# VerdiRT7_Sensor.net
KiCad netlist of a schematic drawn in EAGLE
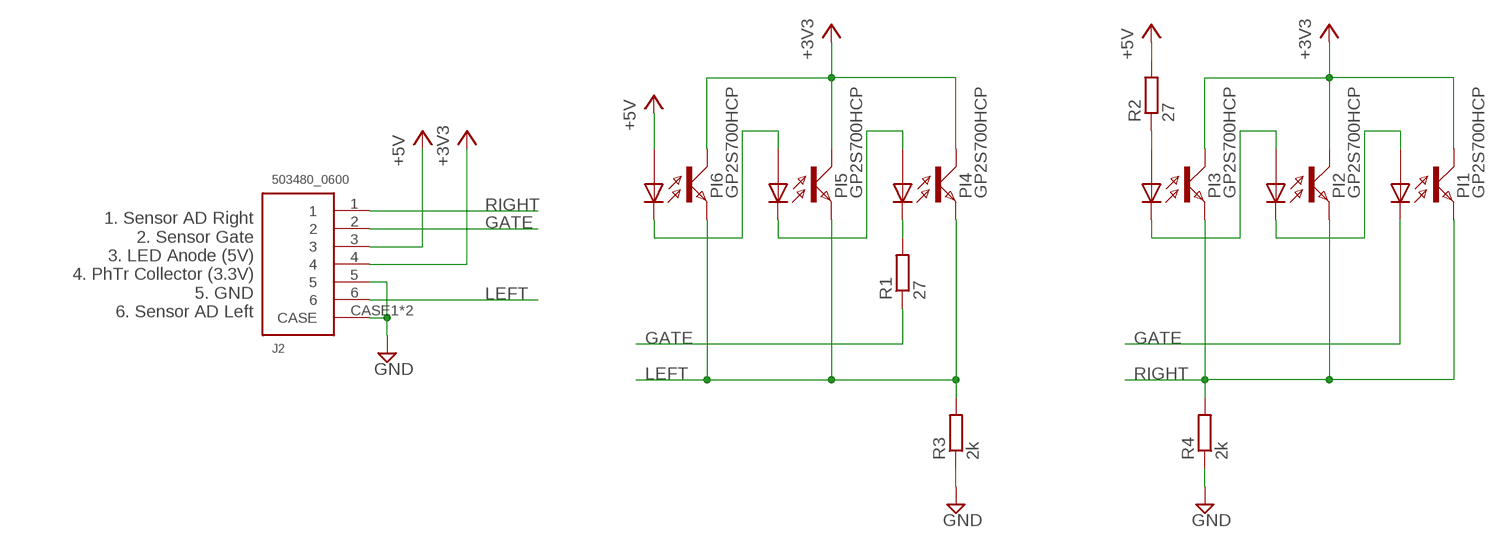
[diagram p0: schematic, sheet 1]

(export (version "E")
  (design (tool "Eeschema 10.0.6"))
  (components
    (comp (ref "J2")
      (value "503480_0600")
      (footprint "eagle-import:0600")
      (libsource (lib "eagle-import") (part "503480_0600"))
    )
    (comp (ref "PI1")
      (value "GP2S700HCP")
      (footprint "eagle-import:GP2S700")
      (libsource (lib "eagle-import") (part "GP2S700HCP"))
    )
    (comp (ref "PI2")
      (value "GP2S700HCP")
      (footprint "eagle-import:GP2S700")
      (libsource (lib "eagle-import") (part "GP2S700HCP"))
    )
    (comp (ref "PI3")
      (value "GP2S700HCP")
      (footprint "eagle-import:GP2S700")
      (libsource (lib "eagle-import") (part "GP2S700HCP"))
    )
    (comp (ref "PI4")
      (value "GP2S700HCP")
      (footprint "eagle-import:GP2S700")
      (libsource (lib "eagle-import") (part "GP2S700HCP"))
    )
    (comp (ref "PI5")
      (value "GP2S700HCP")
      (footprint "eagle-import:GP2S700")
      (libsource (lib "eagle-import") (part "GP2S700HCP"))
    )
    (comp (ref "PI6")
      (value "GP2S700HCP")
      (footprint "eagle-import:GP2S700")
      (libsource (lib "eagle-import") (part "GP2S700HCP"))
    )
    (comp (ref "R1")
      (value "27")
      (footprint "eagle-import:R0603")
      (libsource (lib "eagle-import") (part "R-EU_R0603"))
    )
    (comp (ref "R2")
      (value "27")
      (footprint "eagle-import:R0603")
      (libsource (lib "eagle-import") (part "R-EU_R0603"))
    )
    (comp (ref "R3")
      (value "2k")
      (footprint "eagle-import:R0603")
      (libsource (lib "eagle-import") (part "R-EU_R0603"))
    )
    (comp (ref "R4")
      (value "2k")
      (footprint "eagle-import:R0603")
      (libsource (lib "eagle-import") (part "R-EU_R0603"))
    )
  )
  (nets
    (net (code "1") (name "+3V3") (class "Default")
      (node (ref "J2") (pin "4") (pinfunction "4_4") (pintype "bidirectional"))
      (node (ref "PI1") (pin "COLLECTOR") (pinfunction "COLLECTOR_COLLECTOR") (pintype "passive"))
      (node (ref "PI2") (pin "COLLECTOR") (pinfunction "COLLECTOR_COLLECTOR") (pintype "passive"))
      (node (ref "PI3") (pin "COLLECTOR") (pinfunction "COLLECTOR_COLLECTOR") (pintype "passive"))
      (node (ref "PI4") (pin "COLLECTOR") (pinfunction "COLLECTOR_COLLECTOR") (pintype "passive"))
      (node (ref "PI5") (pin "COLLECTOR") (pinfunction "COLLECTOR_COLLECTOR") (pintype "passive"))
      (node (ref "PI6") (pin "COLLECTOR") (pinfunction "COLLECTOR_COLLECTOR") (pintype "passive"))
    )
    (net (code "2") (name "+5V") (class "Default")
      (node (ref "J2") (pin "3") (pinfunction "3_3") (pintype "bidirectional"))
      (node (ref "PI6") (pin "ANODE") (pinfunction "ANODE_ANODE") (pintype "passive"))
      (node (ref "R2") (pin "2") (pinfunction "2_2") (pintype "passive"))
    )
    (net (code "3") (name "/GATE") (class "Default")
      (node (ref "J2") (pin "2") (pinfunction "2_2") (pintype "bidirectional"))
      (node (ref "PI1") (pin "CATHODE") (pinfunction "CATHODE_CATHODE") (pintype "passive"))
      (node (ref "R1") (pin "1") (pinfunction "1_1") (pintype "passive"))
    )
    (net (code "4") (name "/LEFT") (class "Default")
      (node (ref "J2") (pin "6") (pinfunction "6_6") (pintype "bidirectional"))
      (node (ref "PI4") (pin "EMITTER") (pinfunction "EMITTER_EMITTER") (pintype "passive"))
      (node (ref "PI5") (pin "EMITTER") (pinfunction "EMITTER_EMITTER") (pintype "passive"))
      (node (ref "PI6") (pin "EMITTER") (pinfunction "EMITTER_EMITTER") (pintype "passive"))
      (node (ref "R3") (pin "2") (pinfunction "2_2") (pintype "passive"))
    )
    (net (code "5") (name "/RIGHT") (class "Default")
      (node (ref "J2") (pin "1") (pinfunction "1_1") (pintype "bidirectional"))
      (node (ref "PI1") (pin "EMITTER") (pinfunction "EMITTER_EMITTER") (pintype "passive"))
      (node (ref "PI2") (pin "EMITTER") (pinfunction "EMITTER_EMITTER") (pintype "passive"))
      (node (ref "PI3") (pin "EMITTER") (pinfunction "EMITTER_EMITTER") (pintype "passive"))
      (node (ref "R4") (pin "2") (pinfunction "2_2") (pintype "passive"))
    )
    (net (code "6") (name "GND") (class "Default")
      (node (ref "J2") (pin "5") (pinfunction "5_5") (pintype "bidirectional"))
      (node (ref "J2") (pin "CASE1") (pinfunction "CASE_CASE1") (pintype "bidirectional"))
      (node (ref "J2") (pin "CASE2") (pinfunction "CASE_CASE2") (pintype "bidirectional"))
      (node (ref "R3") (pin "1") (pinfunction "1_1") (pintype "passive"))
      (node (ref "R4") (pin "1") (pinfunction "1_1") (pintype "passive"))
    )
    (net (code "7") (name "Net-(PI1-PadANODE)") (class "Default")
      (node (ref "PI1") (pin "ANODE") (pinfunction "ANODE_ANODE") (pintype "passive"))
      (node (ref "PI2") (pin "CATHODE") (pinfunction "CATHODE_CATHODE") (pintype "passive"))
    )
    (net (code "8") (name "Net-(PI2-PadANODE)") (class "Default")
      (node (ref "PI2") (pin "ANODE") (pinfunction "ANODE_ANODE") (pintype "passive"))
      (node (ref "PI3") (pin "CATHODE") (pinfunction "CATHODE_CATHODE") (pintype "passive"))
    )
    (net (code "9") (name "Net-(PI3-PadANODE)") (class "Default")
      (node (ref "PI3") (pin "ANODE") (pinfunction "ANODE_ANODE") (pintype "passive"))
      (node (ref "R2") (pin "1") (pinfunction "1_1") (pintype "passive"))
    )
    (net (code "10") (name "Net-(PI4-PadANODE)") (class "Default")
      (node (ref "PI4") (pin "ANODE") (pinfunction "ANODE_ANODE") (pintype "passive"))
      (node (ref "PI5") (pin "CATHODE") (pinfunction "CATHODE_CATHODE") (pintype "passive"))
    )
    (net (code "11") (name "Net-(PI4-PadCATHODE)") (class "Default")
      (node (ref "PI4") (pin "CATHODE") (pinfunction "CATHODE_CATHODE") (pintype "passive"))
      (node (ref "R1") (pin "2") (pinfunction "2_2") (pintype "passive"))
    )
    (net (code "12") (name "Net-(PI5-PadANODE)") (class "Default")
      (node (ref "PI5") (pin "ANODE") (pinfunction "ANODE_ANODE") (pintype "passive"))
      (node (ref "PI6") (pin "CATHODE") (pinfunction "CATHODE_CATHODE") (pintype "passive"))
    )
  )
)
